# SE2D_v1_0_0.net
KiCad netlist of a schematic drawn in Altium Designer
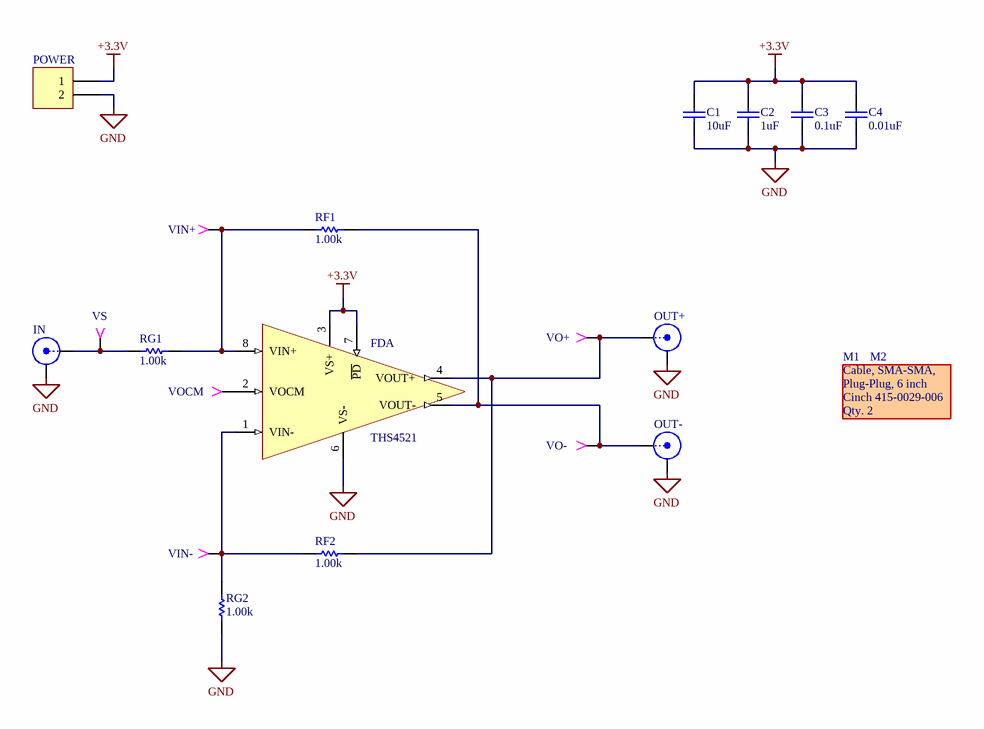
[diagram p0: SE2D v1.0.0.SchDoc]

(export (version "E")
  (design (tool "Eeschema 10.0.6"))
  (components
    (comp (ref "C1")
      (value "10uF")
      (footprint "0603(1608)")
      (fields
        (field (name "MANF") "Samsung Electro-Mechanics")
        (field (name "TOLERANCE") "20")
        (field (name "VOLTAGE") "25")
        (field (name "MODIFIED BY") "sotterbacher")
        (field (name "APPROVED") "True")
      )
      (libsource (lib "MENG Database Library VPN") (part "Cap"))
    )
    (comp (ref "C2")
      (value "1uF")
      (footprint "0603(1608)")
      (fields
        (field (name "MANF") "Taiyo Yuden")
        (field (name "TOLERANCE") "10")
        (field (name "VOLTAGE") "25")
        (field (name "MODIFIED BY") "pmarcus")
        (field (name "APPROVED") "True")
      )
      (libsource (lib "MENG Database Library VPN") (part "Cap"))
    )
    (comp (ref "C3")
      (value "0.1uF")
      (footprint "0603(1608)")
      (fields
        (field (name "MANF") "Samsung Electro-Mechanics")
        (field (name "TOLERANCE") "10")
        (field (name "VOLTAGE") "50")
        (field (name "MODIFIED BY") "pmarcus")
        (field (name "APPROVED") "True")
      )
      (libsource (lib "MENG Database Library VPN") (part "Cap"))
    )
    (comp (ref "C4")
      (value "0.01uF")
      (footprint "0603(1608)")
      (fields
        (field (name "MANF") "Samsung Electro-Mechanics")
        (field (name "TOLERANCE") "10")
        (field (name "VOLTAGE") "50")
        (field (name "MODIFIED BY") "jrowley")
        (field (name "APPROVED") "False")
      )
      (libsource (lib "MENG Database Library VPN") (part "Cap"))
    )
    (comp (ref "FDA")
      (value "THS4521")
      (footprint "TI_D0008A")
      (fields (field (name "MANF") "Texas Instruments"))
      (libsource (lib "SE2D v1.0") (part "THS4521IDR"))
    )
    (comp (ref "IN")
      (value "R/A")
      (footprint "BNC - Right Angle")
      (fields
        (field (name "MANF") "Tyco")
        (field (name "MODIFIED BY") "pmarcus")
        (field (name "APPROVED") "True")
      )
      (libsource (lib "MENG Database Library VPN") (part "BNC"))
    )
    (comp (ref "M1")
      (value "Qty. 2")
      (fields
        (field (name "MANF") "Cinch Connectivity Solutions Johnson")
        (field (name "CLASS") "Cable, SMA-SMA,")
        (field (name "TYPE") "Plug-Plug, 6 inch")
        (field (name "OTHER") "Cinch 415-0029-006")
      )
      (libsource (lib "SE2D v1.0") (part "SMA PLUG-PLUG 6"))
    )
    (comp (ref "M2")
      (value "Qty. 2")
      (fields
        (field (name "MANF") "Cinch Connectivity Solutions Johnson")
        (field (name "CLASS") "Cable, SMA-SMA,")
        (field (name "TYPE") "Plug-Plug, 6 inch")
        (field (name "OTHER") "Cinch 415-0029-006")
      )
      (libsource (lib "SE2D v1.0") (part "SMA PLUG-PLUG 6"))
    )
    (comp (ref "OUT+")
      (value "SMA-J-P-H-ST-EM1")
      (footprint "SE2D v1.0:*SMA-J-P-H-ST-EM1_SMA-J-P-H-ST-EM1(Primary)")
      (fields (field (name "MANF") "Samtec Inc."))
      (libsource (lib "SE2D v1.0") (part "SMA-J-P-H-ST-EM1"))
    )
    (comp (ref "OUT-")
      (value "SMA-J-P-H-ST-EM1")
      (footprint "SE2D v1.0:*SMA-J-P-H-ST-EM1_SMA-J-P-H-ST-EM1(Primary)")
      (fields (field (name "MANF") "Samtec Inc."))
      (libsource (lib "SE2D v1.0") (part "SMA-J-P-H-ST-EM1"))
    )
    (comp (ref "POWER")
      (value "*")
      (footprint "0.1HDR1X2P")
      (fields
        (field (name "MANF") "Molex")
        (field (name "VOLTAGE") "250")
        (field (name "MODIFIED BY") "jrowley")
        (field (name "APPROVED") "False")
      )
      (libsource (lib "MENG Database Library VPN") (part "Header 2"))
    )
    (comp (ref "RF1")
      (value "1.00k")
      (footprint "0603(1608)")
      (fields
        (field (name "MANF") "Yageo")
        (field (name "TOLERANCE") "1")
        (field (name "POWER") "0.1")
        (field (name "MODIFIED BY") "khall")
        (field (name "APPROVED") "False")
      )
      (libsource (lib "MENG Database Library VPN") (part "Res1"))
    )
    (comp (ref "RF2")
      (value "1.00k")
      (footprint "0603(1608)")
      (fields
        (field (name "MANF") "Yageo")
        (field (name "TOLERANCE") "1")
        (field (name "POWER") "0.1")
        (field (name "MODIFIED BY") "khall")
        (field (name "APPROVED") "False")
      )
      (libsource (lib "MENG Database Library VPN") (part "Res1"))
    )
    (comp (ref "RG1")
      (value "1.00k")
      (footprint "0603(1608)")
      (fields
        (field (name "MANF") "Yageo")
        (field (name "TOLERANCE") "1")
        (field (name "POWER") "0.1")
        (field (name "MODIFIED BY") "khall")
        (field (name "APPROVED") "False")
      )
      (libsource (lib "MENG Database Library VPN") (part "Res1"))
    )
    (comp (ref "RG2")
      (value "1.00k")
      (footprint "0603(1608)")
      (fields
        (field (name "MANF") "Yageo")
        (field (name "TOLERANCE") "1")
        (field (name "POWER") "0.1")
        (field (name "MODIFIED BY") "khall")
        (field (name "APPROVED") "False")
      )
      (libsource (lib "MENG Database Library VPN") (part "Res1"))
    )
    (comp (ref "VIN+")
      (value "TP")
      (footprint "TESTPOINT024")
      (fields
        (field (name "MANF") "Keystone Electronics")
        (field (name "APPROVED") "True")
        (field (name "MODIFIED BY") "sotterbacher")
      )
      (libsource (lib "MENG Database Library VPN") (part "TP"))
    )
    (comp (ref "VIN-")
      (value "TP")
      (footprint "TESTPOINT024")
      (fields
        (field (name "MANF") "Keystone Electronics")
        (field (name "APPROVED") "True")
        (field (name "MODIFIED BY") "sotterbacher")
      )
      (libsource (lib "MENG Database Library VPN") (part "TP"))
    )
    (comp (ref "VO+")
      (value "TP")
      (footprint "TESTPOINT024")
      (fields
        (field (name "MANF") "Keystone Electronics")
        (field (name "APPROVED") "True")
        (field (name "MODIFIED BY") "sotterbacher")
      )
      (libsource (lib "MENG Database Library VPN") (part "TP"))
    )
    (comp (ref "VO-")
      (value "TP")
      (footprint "TESTPOINT024")
      (fields
        (field (name "MANF") "Keystone Electronics")
        (field (name "APPROVED") "True")
        (field (name "MODIFIED BY") "sotterbacher")
      )
      (libsource (lib "MENG Database Library VPN") (part "TP"))
    )
    (comp (ref "VOCM")
      (value "TP")
      (footprint "TESTPOINT024")
      (fields
        (field (name "MANF") "Keystone Electronics")
        (field (name "APPROVED") "True")
        (field (name "MODIFIED BY") "sotterbacher")
      )
      (libsource (lib "MENG Database Library VPN") (part "TP"))
    )
    (comp (ref "VS")
      (value "TP")
      (footprint "TESTPOINT024")
      (fields
        (field (name "MANF") "Keystone Electronics")
        (field (name "APPROVED") "True")
        (field (name "MODIFIED BY") "sotterbacher")
      )
      (libsource (lib "MENG Database Library VPN") (part "TP"))
    )
  )
  (nets
    (net (code "1") (name "+3.3V") (class "Default")
      (node (ref "C1") (pin "2") (pinfunction "2_2") (pintype "passive"))
      (node (ref "C2") (pin "2") (pinfunction "2_2") (pintype "passive"))
      (node (ref "C3") (pin "2") (pinfunction "2_2") (pintype "passive"))
      (node (ref "C4") (pin "2") (pinfunction "2_2") (pintype "passive"))
      (node (ref "FDA") (pin "3") (pinfunction "VS+_3") (pintype "power_in"))
      (node (ref "FDA") (pin "7") (pinfunction "~{PD}_7") (pintype "input"))
      (node (ref "POWER") (pin "1") (pinfunction "1_1") (pintype "passive"))
    )
    (net (code "2") (name "GND") (class "Default")
      (node (ref "C1") (pin "1") (pinfunction "1_1") (pintype "passive"))
      (node (ref "C2") (pin "1") (pinfunction "1_1") (pintype "passive"))
      (node (ref "C3") (pin "1") (pinfunction "1_1") (pintype "passive"))
      (node (ref "C4") (pin "1") (pinfunction "1_1") (pintype "passive"))
      (node (ref "FDA") (pin "6") (pinfunction "VS-_6") (pintype "power_in"))
      (node (ref "IN") (pin "2") (pinfunction "Y_2") (pintype "passive"))
      (node (ref "OUT+") (pin "2") (pinfunction "Y_2") (pintype "passive"))
      (node (ref "OUT-") (pin "2") (pinfunction "Y_2") (pintype "passive"))
      (node (ref "POWER") (pin "2") (pinfunction "2_2") (pintype "passive"))
      (node (ref "RG2") (pin "1") (pinfunction "1_1") (pintype "passive"))
    )
    (net (code "3") (name "Net-(FDA-VIN+)") (class "Default")
      (node (ref "FDA") (pin "8") (pinfunction "VIN+_8") (pintype "input"))
      (node (ref "RF1") (pin "1") (pinfunction "1_1") (pintype "passive"))
      (node (ref "RG1") (pin "2") (pinfunction "2_2") (pintype "passive"))
      (node (ref "VIN+") (pin "1") (pinfunction "1_1") (pintype "passive"))
    )
    (net (code "4") (name "Net-(FDA-VIN-)") (class "Default")
      (node (ref "FDA") (pin "1") (pinfunction "VIN-_1") (pintype "input"))
      (node (ref "RF2") (pin "1") (pinfunction "1_1") (pintype "passive"))
      (node (ref "RG2") (pin "2") (pinfunction "2_2") (pintype "passive"))
      (node (ref "VIN-") (pin "1") (pinfunction "1_1") (pintype "passive"))
    )
    (net (code "5") (name "Net-(FDA-VOCM)") (class "Default")
      (node (ref "FDA") (pin "2") (pinfunction "VOCM_2") (pintype "input"))
      (node (ref "VOCM") (pin "1") (pinfunction "1_1") (pintype "passive"))
    )
    (net (code "6") (name "Net-(FDA-VOUT+)") (class "Default")
      (node (ref "FDA") (pin "4") (pinfunction "VOUT+_4") (pintype "output"))
      (node (ref "OUT+") (pin "1") (pinfunction "X_1") (pintype "passive"))
      (node (ref "RF2") (pin "2") (pinfunction "2_2") (pintype "passive"))
      (node (ref "VO+") (pin "1") (pinfunction "1_1") (pintype "passive"))
    )
    (net (code "7") (name "Net-(FDA-VOUT-)") (class "Default")
      (node (ref "FDA") (pin "5") (pinfunction "VOUT-_5") (pintype "output"))
      (node (ref "OUT-") (pin "1") (pinfunction "X_1") (pintype "passive"))
      (node (ref "RF1") (pin "2") (pinfunction "2_2") (pintype "passive"))
      (node (ref "VO-") (pin "1") (pinfunction "1_1") (pintype "passive"))
    )
    (net (code "8") (name "Net-(IN-X)") (class "Default")
      (node (ref "IN") (pin "1") (pinfunction "X_1") (pintype "passive"))
      (node (ref "RG1") (pin "1") (pinfunction "1_1") (pintype "passive"))
      (node (ref "VS") (pin "1") (pinfunction "1_1") (pintype "passive"))
    )
  )
)
